# NavCom_Board_3.net
KiCad netlist of a schematic drawn in EAGLE
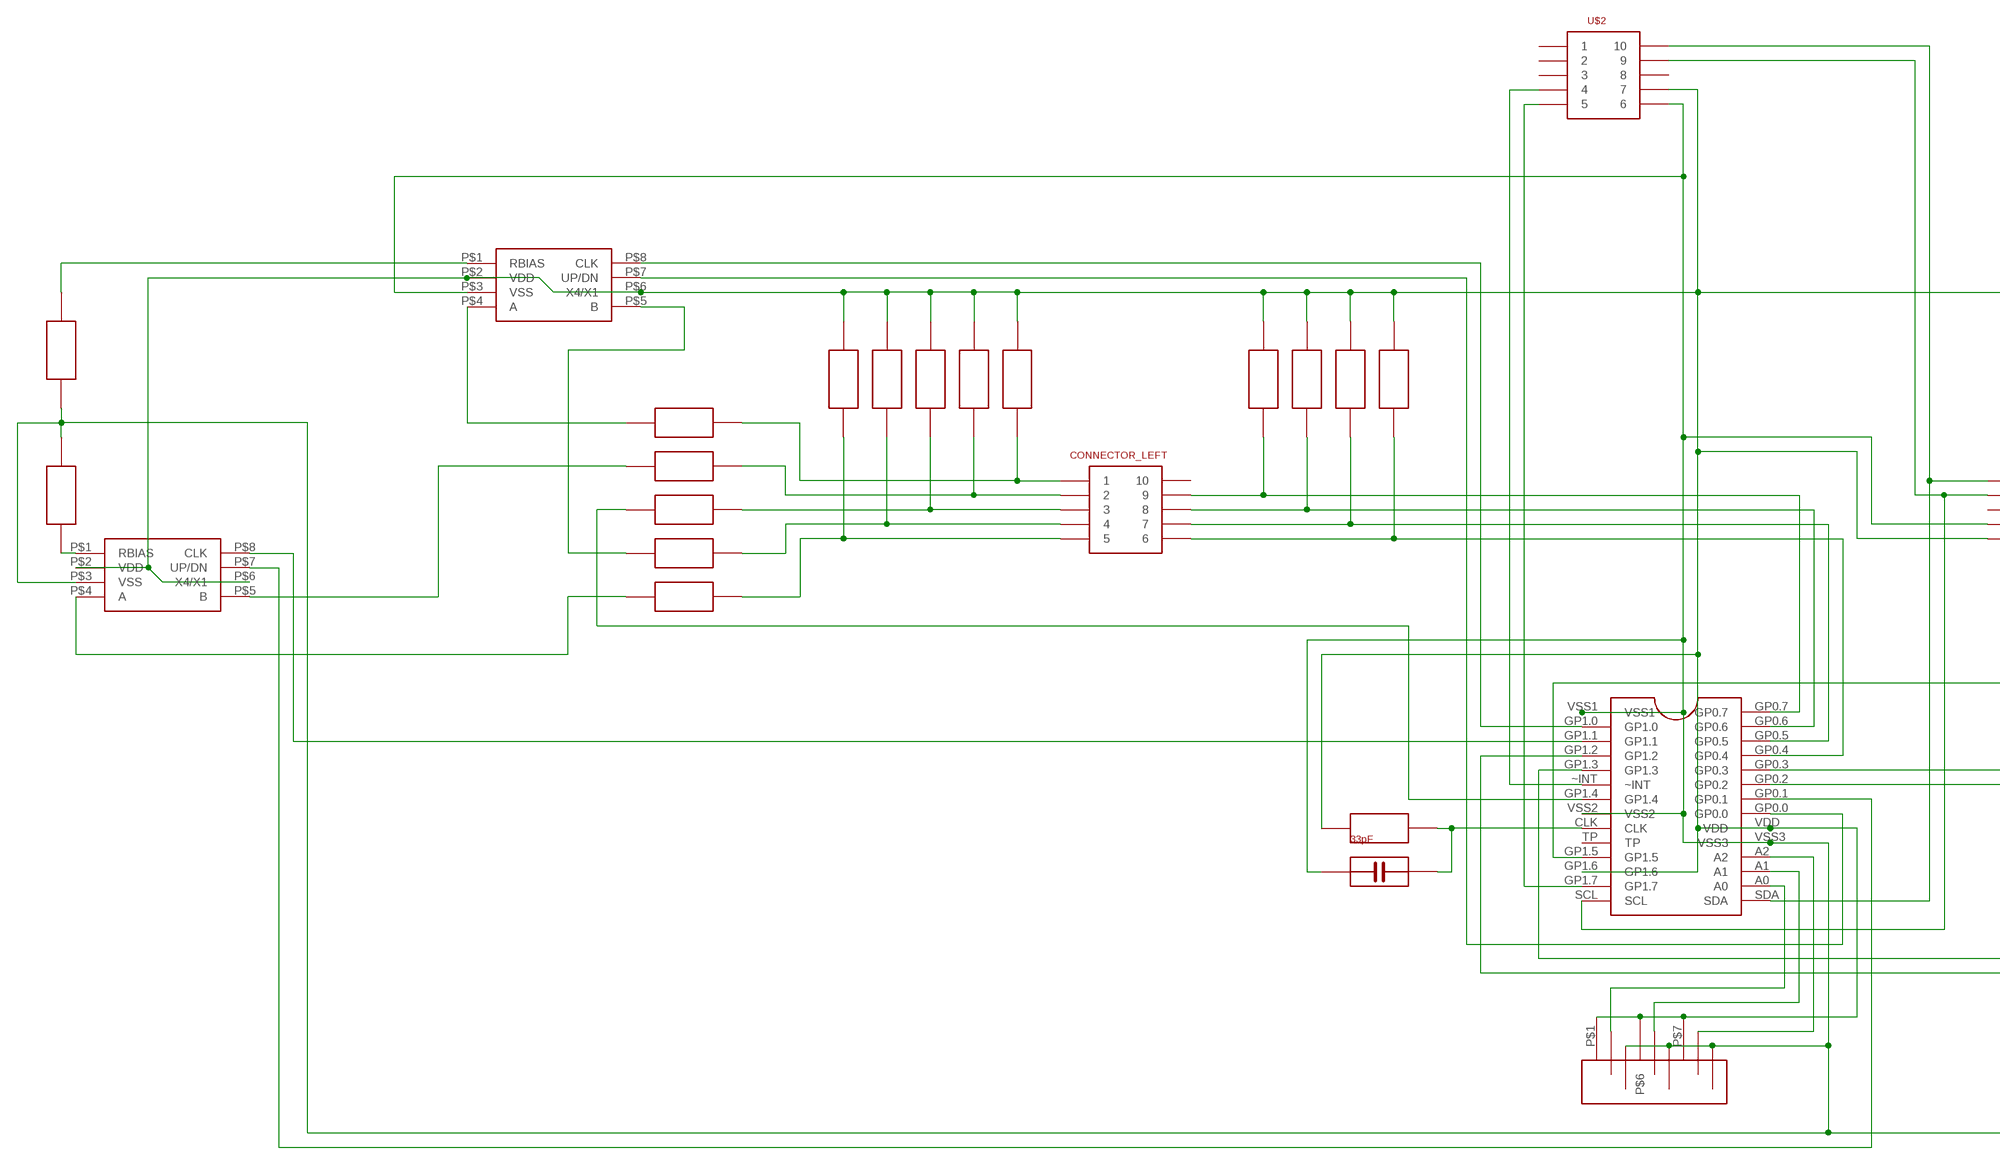
[diagram p0: schematic, sheet 1, part 1 of 2]
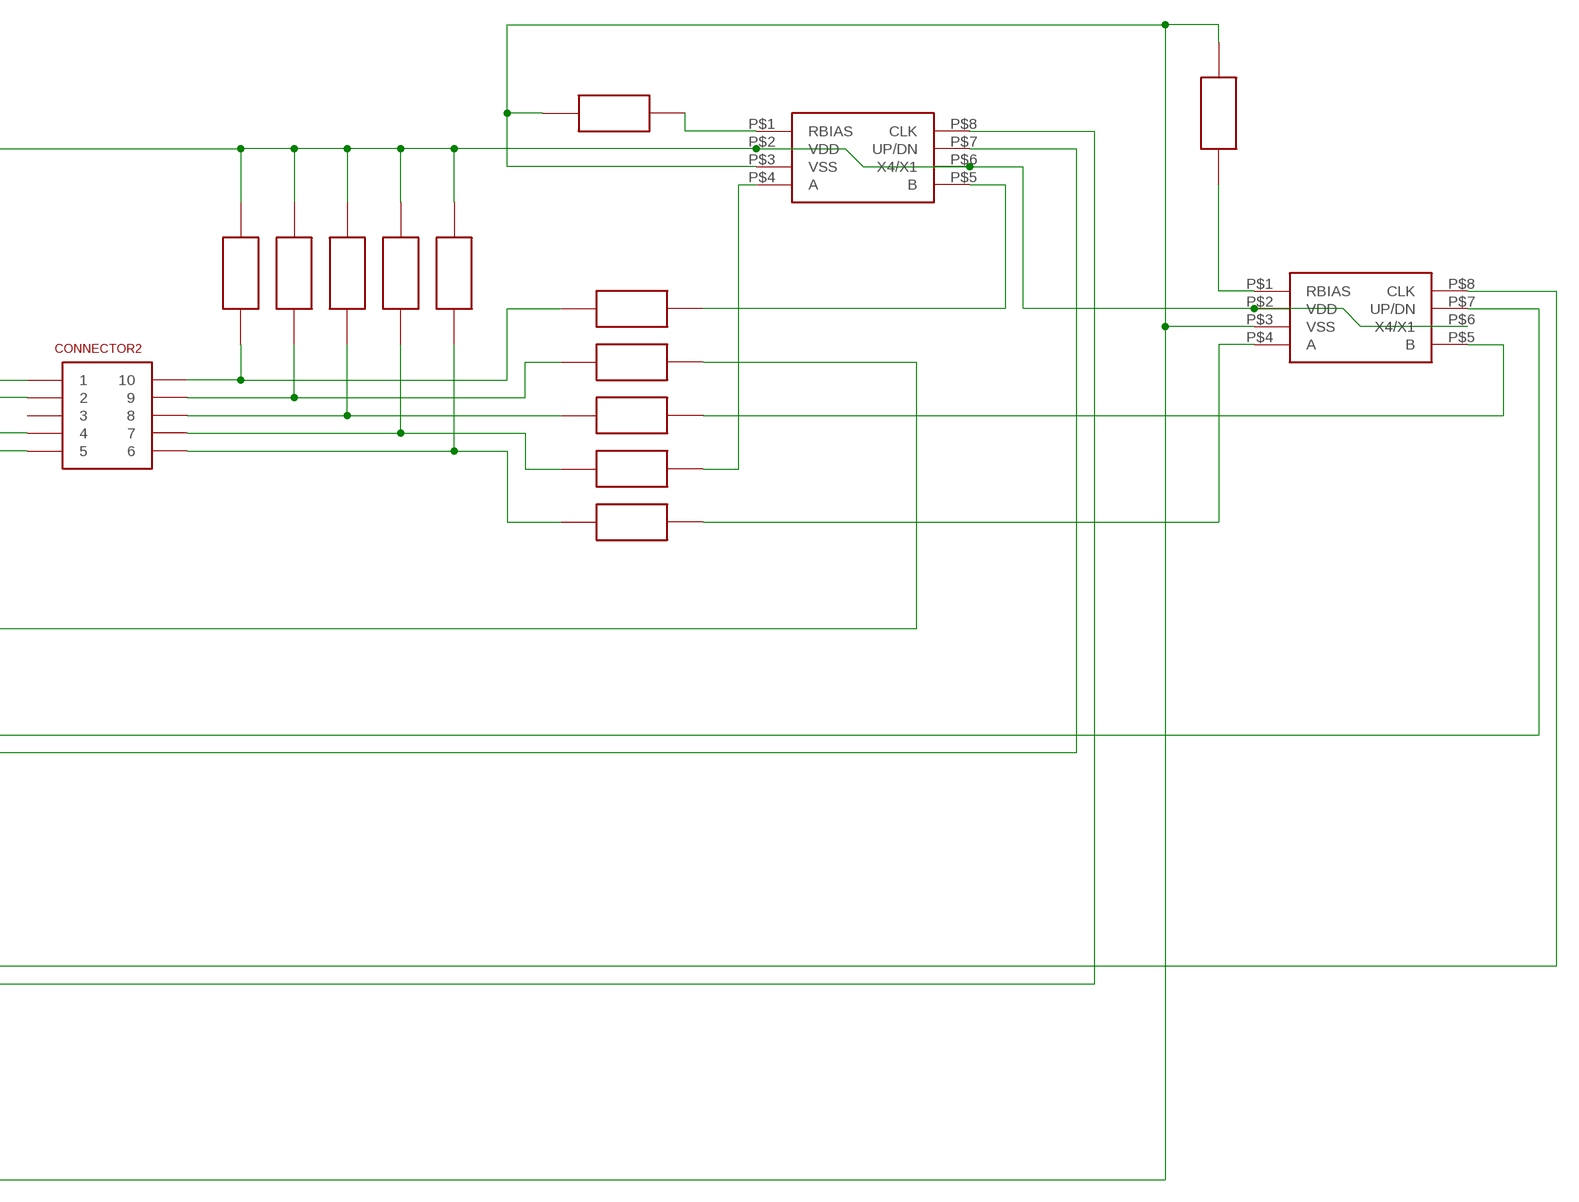
[diagram p1: schematic, sheet 1, part 2 of 2]

(export (version "E")
  (design (tool "Eeschema 10.0.6"))
  (components
    (comp (ref "33PF")
      (value "33pF")
      (footprint "eagle-import:KONDENZATOR")
      (libsource (lib "eagle-import") (part "KONDENZATOR"))
    )
    (comp (ref "CONNECTOR2")
      (value "LISTA_2X5")
      (footprint "eagle-import:LISTA_2X5")
      (libsource (lib "eagle-import") (part "LISTA_2X5"))
    )
    (comp (ref "CONNECTOR_LEFT")
      (value "LISTA_2X5")
      (footprint "eagle-import:LISTA_2X5")
      (libsource (lib "eagle-import") (part "LISTA_2X5"))
    )
    (comp (ref "U$1")
      (value "MCP23016")
      (footprint "eagle-import:MCP23016")
      (libsource (lib "eagle-import") (part "MCP23016"))
    )
    (comp (ref "U$2")
      (value "LISTA_2X5")
      (footprint "eagle-import:LISTA_2X5")
      (libsource (lib "eagle-import") (part "LISTA_2X5"))
    )
    (comp (ref "U$3")
      (value "LS7084")
      (footprint "eagle-import:LS7084")
      (libsource (lib "eagle-import") (part "LS7084"))
    )
    (comp (ref "U$4")
      (value "LS7084")
      (footprint "eagle-import:LS7084")
      (libsource (lib "eagle-import") (part "LS7084"))
    )
    (comp (ref "U$5")
      (value "LS7084")
      (footprint "eagle-import:LS7084")
      (libsource (lib "eagle-import") (part "LS7084"))
    )
    (comp (ref "U$6")
      (value "LS7084")
      (footprint "eagle-import:LS7084")
      (libsource (lib "eagle-import") (part "LS7084"))
    )
    (comp (ref "U$7")
      (value "REZISTOR")
      (footprint "eagle-import:REZISTOR")
      (libsource (lib "eagle-import") (part "REZISTOR"))
    )
    (comp (ref "U$8")
      (value "REZISTOR")
      (footprint "eagle-import:REZISTOR")
      (libsource (lib "eagle-import") (part "REZISTOR"))
    )
    (comp (ref "U$9")
      (value "REZISTOR")
      (footprint "eagle-import:REZISTOR")
      (libsource (lib "eagle-import") (part "REZISTOR"))
    )
    (comp (ref "U$10")
      (value "REZISTOR")
      (footprint "eagle-import:REZISTOR")
      (libsource (lib "eagle-import") (part "REZISTOR"))
    )
    (comp (ref "U$11")
      (value "ADRESA_0..2")
      (footprint "eagle-import:ADRESA_0..2")
      (libsource (lib "eagle-import") (part "ADRESA_0..2"))
    )
    (comp (ref "U$12")
      (value "REZISTOR")
      (footprint "eagle-import:REZISTOR")
      (libsource (lib "eagle-import") (part "REZISTOR"))
    )
    (comp (ref "U$13")
      (value "REZISTOR")
      (footprint "eagle-import:REZISTOR")
      (libsource (lib "eagle-import") (part "REZISTOR"))
    )
    (comp (ref "U$14")
      (value "REZISTOR")
      (footprint "eagle-import:REZISTOR")
      (libsource (lib "eagle-import") (part "REZISTOR"))
    )
    (comp (ref "U$15")
      (value "REZISTOR")
      (footprint "eagle-import:REZISTOR")
      (libsource (lib "eagle-import") (part "REZISTOR"))
    )
    (comp (ref "U$16")
      (value "REZISTOR")
      (footprint "eagle-import:REZISTOR")
      (libsource (lib "eagle-import") (part "REZISTOR"))
    )
    (comp (ref "U$17")
      (value "REZISTOR")
      (footprint "eagle-import:REZISTOR")
      (libsource (lib "eagle-import") (part "REZISTOR"))
    )
    (comp (ref "U$18")
      (value "REZISTOR")
      (footprint "eagle-import:REZISTOR")
      (libsource (lib "eagle-import") (part "REZISTOR"))
    )
    (comp (ref "U$19")
      (value "REZISTOR")
      (footprint "eagle-import:REZISTOR")
      (libsource (lib "eagle-import") (part "REZISTOR"))
    )
    (comp (ref "U$20")
      (value "REZISTOR")
      (footprint "eagle-import:REZISTOR")
      (libsource (lib "eagle-import") (part "REZISTOR"))
    )
    (comp (ref "U$21")
      (value "REZISTOR")
      (footprint "eagle-import:REZISTOR")
      (libsource (lib "eagle-import") (part "REZISTOR"))
    )
    (comp (ref "U$22")
      (value "REZISTOR")
      (footprint "eagle-import:REZISTOR")
      (libsource (lib "eagle-import") (part "REZISTOR"))
    )
    (comp (ref "U$23")
      (value "3.9k")
      (footprint "eagle-import:REZISTOR")
      (libsource (lib "eagle-import") (part "REZISTOR"))
    )
    (comp (ref "U$27")
      (value "470M")
      (footprint "eagle-import:REZISTOR")
      (libsource (lib "eagle-import") (part "REZISTOR"))
    )
    (comp (ref "U$29")
      (value "REZISTOR")
      (footprint "eagle-import:REZISTOR")
      (libsource (lib "eagle-import") (part "REZISTOR"))
    )
    (comp (ref "U$30")
      (value "REZISTOR")
      (footprint "eagle-import:REZISTOR")
      (libsource (lib "eagle-import") (part "REZISTOR"))
    )
    (comp (ref "U$31")
      (value "REZISTOR")
      (footprint "eagle-import:REZISTOR")
      (libsource (lib "eagle-import") (part "REZISTOR"))
    )
    (comp (ref "U$32")
      (value "REZISTOR")
      (footprint "eagle-import:REZISTOR")
      (libsource (lib "eagle-import") (part "REZISTOR"))
    )
    (comp (ref "U$33")
      (value "REZISTOR")
      (footprint "eagle-import:REZISTOR")
      (libsource (lib "eagle-import") (part "REZISTOR"))
    )
    (comp (ref "U$34")
      (value "470M")
      (footprint "eagle-import:REZISTOR")
      (libsource (lib "eagle-import") (part "REZISTOR"))
    )
    (comp (ref "U$35")
      (value "REZISTOR")
      (footprint "eagle-import:REZISTOR")
      (libsource (lib "eagle-import") (part "REZISTOR"))
    )
    (comp (ref "U$36")
      (value "REZISTOR")
      (footprint "eagle-import:REZISTOR")
      (libsource (lib "eagle-import") (part "REZISTOR"))
    )
    (comp (ref "U$38")
      (value "REZISTOR")
      (footprint "eagle-import:REZISTOR")
      (libsource (lib "eagle-import") (part "REZISTOR"))
    )
    (comp (ref "U$39")
      (value "REZISTOR")
      (footprint "eagle-import:REZISTOR")
      (libsource (lib "eagle-import") (part "REZISTOR"))
    )
    (comp (ref "U$40")
      (value "470M")
      (footprint "eagle-import:REZISTOR")
      (libsource (lib "eagle-import") (part "REZISTOR"))
    )
    (comp (ref "U$41")
      (value "470M")
      (footprint "eagle-import:REZISTOR")
      (libsource (lib "eagle-import") (part "REZISTOR"))
    )
  )
  (nets
    (net (code "1") (name "Net-(33PF-PadP$2)") (class "Default")
      (node (ref "33PF") (pin "P$2") (pinfunction "P$2_P$2") (pintype "bidirectional"))
      (node (ref "U$1") (pin "CLK") (pinfunction "CLK_CLK") (pintype "bidirectional"))
      (node (ref "U$23") (pin "P$2") (pinfunction "P$2_P$2") (pintype "bidirectional"))
    )
    (net (code "2") (name "Net-(CONNECTOR2-Pad1)") (class "Default")
      (node (ref "CONNECTOR2") (pin "1") (pinfunction "1_1") (pintype "bidirectional"))
      (node (ref "U$1") (pin "SDA") (pinfunction "SDA_SDA") (pintype "bidirectional"))
      (node (ref "U$2") (pin "10") (pinfunction "10_10") (pintype "bidirectional"))
    )
    (net (code "3") (name "Net-(CONNECTOR2-Pad2)") (class "Default")
      (node (ref "CONNECTOR2") (pin "2") (pinfunction "2_2") (pintype "bidirectional"))
      (node (ref "U$1") (pin "SCL") (pinfunction "SCL_SCL") (pintype "bidirectional"))
      (node (ref "U$2") (pin "9") (pinfunction "9_9") (pintype "bidirectional"))
    )
    (net (code "4") (name "Net-(CONNECTOR2-Pad6)") (class "Default")
      (node (ref "CONNECTOR2") (pin "6") (pinfunction "6_6") (pintype "bidirectional"))
      (node (ref "U$12") (pin "P$1") (pinfunction "P$1_P$1") (pintype "bidirectional"))
      (node (ref "U$33") (pin "P$2") (pinfunction "P$2_P$2") (pintype "bidirectional"))
    )
    (net (code "5") (name "Net-(CONNECTOR2-Pad7)") (class "Default")
      (node (ref "CONNECTOR2") (pin "7") (pinfunction "7_7") (pintype "bidirectional"))
      (node (ref "U$17") (pin "P$1") (pinfunction "P$1_P$1") (pintype "bidirectional"))
      (node (ref "U$32") (pin "P$2") (pinfunction "P$2_P$2") (pintype "bidirectional"))
    )
    (net (code "6") (name "Net-(CONNECTOR2-Pad8)") (class "Default")
      (node (ref "CONNECTOR2") (pin "8") (pinfunction "8_8") (pintype "bidirectional"))
      (node (ref "U$10") (pin "P$1") (pinfunction "P$1_P$1") (pintype "bidirectional"))
      (node (ref "U$31") (pin "P$2") (pinfunction "P$2_P$2") (pintype "bidirectional"))
    )
    (net (code "7") (name "Net-(CONNECTOR2-Pad9)") (class "Default")
      (node (ref "CONNECTOR2") (pin "9") (pinfunction "9_9") (pintype "bidirectional"))
      (node (ref "U$30") (pin "P$2") (pinfunction "P$2_P$2") (pintype "bidirectional"))
      (node (ref "U$9") (pin "P$1") (pinfunction "P$1_P$1") (pintype "bidirectional"))
    )
    (net (code "8") (name "Net-(CONNECTOR2-Pad10)") (class "Default")
      (node (ref "CONNECTOR2") (pin "10") (pinfunction "10_10") (pintype "bidirectional"))
      (node (ref "U$29") (pin "P$2") (pinfunction "P$2_P$2") (pintype "bidirectional"))
      (node (ref "U$7") (pin "P$1") (pinfunction "P$1_P$1") (pintype "bidirectional"))
    )
    (net (code "9") (name "Net-(CONNECTOR_LEFT-Pad1)") (class "Default")
      (node (ref "CONNECTOR_LEFT") (pin "1") (pinfunction "1_1") (pintype "bidirectional"))
      (node (ref "U$16") (pin "P$2") (pinfunction "P$2_P$2") (pintype "bidirectional"))
      (node (ref "U$35") (pin "P$2") (pinfunction "P$2_P$2") (pintype "bidirectional"))
    )
    (net (code "10") (name "Net-(CONNECTOR_LEFT-Pad2)") (class "Default")
      (node (ref "CONNECTOR_LEFT") (pin "2") (pinfunction "2_2") (pintype "bidirectional"))
      (node (ref "U$13") (pin "P$2") (pinfunction "P$2_P$2") (pintype "bidirectional"))
      (node (ref "U$36") (pin "P$2") (pinfunction "P$2_P$2") (pintype "bidirectional"))
    )
    (net (code "11") (name "Net-(CONNECTOR_LEFT-Pad3)") (class "Default")
      (node (ref "CONNECTOR_LEFT") (pin "3") (pinfunction "3_3") (pintype "bidirectional"))
      (node (ref "U$14") (pin "P$2") (pinfunction "P$2_P$2") (pintype "bidirectional"))
      (node (ref "U$22") (pin "P$2") (pinfunction "P$2_P$2") (pintype "bidirectional"))
    )
    (net (code "12") (name "Net-(CONNECTOR_LEFT-Pad4)") (class "Default")
      (node (ref "CONNECTOR_LEFT") (pin "4") (pinfunction "4_4") (pintype "bidirectional"))
      (node (ref "U$15") (pin "P$2") (pinfunction "P$2_P$2") (pintype "bidirectional"))
      (node (ref "U$38") (pin "P$2") (pinfunction "P$2_P$2") (pintype "bidirectional"))
    )
    (net (code "13") (name "Net-(CONNECTOR_LEFT-Pad5)") (class "Default")
      (node (ref "CONNECTOR_LEFT") (pin "5") (pinfunction "5_5") (pintype "bidirectional"))
      (node (ref "U$18") (pin "P$2") (pinfunction "P$2_P$2") (pintype "bidirectional"))
      (node (ref "U$39") (pin "P$2") (pinfunction "P$2_P$2") (pintype "bidirectional"))
    )
    (net (code "14") (name "Net-(CONNECTOR_LEFT-Pad6)") (class "Default")
      (node (ref "CONNECTOR_LEFT") (pin "6") (pinfunction "6_6") (pintype "bidirectional"))
      (node (ref "U$1") (pin "GP0.4") (pinfunction "GP0.4_GP0.4") (pintype "bidirectional"))
      (node (ref "U$21") (pin "P$2") (pinfunction "P$2_P$2") (pintype "bidirectional"))
    )
    (net (code "15") (name "Net-(CONNECTOR_LEFT-Pad7)") (class "Default")
      (node (ref "CONNECTOR_LEFT") (pin "7") (pinfunction "7_7") (pintype "bidirectional"))
      (node (ref "U$1") (pin "GP0.5") (pinfunction "GP0.5_GP0.5") (pintype "bidirectional"))
      (node (ref "U$20") (pin "P$2") (pinfunction "P$2_P$2") (pintype "bidirectional"))
    )
    (net (code "16") (name "Net-(CONNECTOR_LEFT-Pad8)") (class "Default")
      (node (ref "CONNECTOR_LEFT") (pin "8") (pinfunction "8_8") (pintype "bidirectional"))
      (node (ref "U$1") (pin "GP0.6") (pinfunction "GP0.6_GP0.6") (pintype "bidirectional"))
      (node (ref "U$19") (pin "P$2") (pinfunction "P$2_P$2") (pintype "bidirectional"))
    )
    (net (code "17") (name "Net-(CONNECTOR_LEFT-Pad9)") (class "Default")
      (node (ref "CONNECTOR_LEFT") (pin "9") (pinfunction "9_9") (pintype "bidirectional"))
      (node (ref "U$1") (pin "GP0.7") (pinfunction "GP0.7_GP0.7") (pintype "bidirectional"))
      (node (ref "U$8") (pin "P$2") (pinfunction "P$2_P$2") (pintype "bidirectional"))
    )
    (net (code "18") (name "Net-(U$1-PadA0)") (class "Default")
      (node (ref "U$1") (pin "A0") (pinfunction "A0_A0") (pintype "bidirectional"))
      (node (ref "U$11") (pin "P$2") (pinfunction "P$2_P$2") (pintype "bidirectional"))
    )
    (net (code "19") (name "Net-(U$1-PadA1)") (class "Default")
      (node (ref "U$1") (pin "A1") (pinfunction "A1_A1") (pintype "bidirectional"))
      (node (ref "U$11") (pin "P$5") (pinfunction "P$5_P$5") (pintype "bidirectional"))
    )
    (net (code "20") (name "Net-(U$1-PadA2)") (class "Default")
      (node (ref "U$1") (pin "A2") (pinfunction "A2_A2") (pintype "bidirectional"))
      (node (ref "U$11") (pin "P$8") (pinfunction "P$8_P$8") (pintype "bidirectional"))
    )
    (net (code "21") (name "Net-(U$1-PadGP1.4)") (class "Default")
      (node (ref "U$1") (pin "GP1.4") (pinfunction "GP1.4_GP1.4") (pintype "bidirectional"))
      (node (ref "U$22") (pin "P$1") (pinfunction "P$1_P$1") (pintype "bidirectional"))
    )
    (net (code "22") (name "Net-(U$1-PadGP1.5)") (class "Default")
      (node (ref "U$1") (pin "GP1.5") (pinfunction "GP1.5_GP1.5") (pintype "bidirectional"))
      (node (ref "U$30") (pin "P$1") (pinfunction "P$1_P$1") (pintype "bidirectional"))
    )
    (net (code "23") (name "Net-(U$1-PadGP1.7)") (class "Default")
      (node (ref "U$1") (pin "GP1.7") (pinfunction "GP1.7_GP1.7") (pintype "bidirectional"))
      (node (ref "U$2") (pin "5") (pinfunction "5_5") (pintype "bidirectional"))
    )
    (net (code "24") (name "Net-(U$1-~{INT})") (class "Default")
      (node (ref "U$1") (pin "~INT") (pinfunction "~{INT}_~INT") (pintype "bidirectional"))
      (node (ref "U$2") (pin "4") (pinfunction "4_4") (pintype "bidirectional"))
    )
    (net (code "25") (name "Net-(U$3-A)") (class "Default")
      (node (ref "U$3") (pin "P$4") (pinfunction "A_P$4") (pintype "bidirectional"))
      (node (ref "U$35") (pin "P$1") (pinfunction "P$1_P$1") (pintype "bidirectional"))
    )
    (net (code "26") (name "Net-(U$3-B)") (class "Default")
      (node (ref "U$3") (pin "P$5") (pinfunction "B_P$5") (pintype "bidirectional"))
      (node (ref "U$38") (pin "P$1") (pinfunction "P$1_P$1") (pintype "bidirectional"))
    )
    (net (code "27") (name "Net-(U$3-CLK)") (class "Default")
      (node (ref "U$1") (pin "GP1.0") (pinfunction "GP1.0_GP1.0") (pintype "bidirectional"))
      (node (ref "U$3") (pin "P$8") (pinfunction "CLK_P$8") (pintype "bidirectional"))
    )
    (net (code "28") (name "Net-(U$3-RBIAS)") (class "Default")
      (node (ref "U$3") (pin "P$1") (pinfunction "RBIAS_P$1") (pintype "bidirectional"))
      (node (ref "U$40") (pin "P$2") (pinfunction "P$2_P$2") (pintype "bidirectional"))
    )
    (net (code "29") (name "Net-(U$3-UP{slash}DN)") (class "Default")
      (node (ref "U$1") (pin "GP0.0") (pinfunction "GP0.0_GP0.0") (pintype "bidirectional"))
      (node (ref "U$3") (pin "P$7") (pinfunction "UP/DN_P$7") (pintype "bidirectional"))
    )
    (net (code "30") (name "Net-(U$3-VDD)") (class "Default")
      (node (ref "CONNECTOR2") (pin "5") (pinfunction "5_5") (pintype "bidirectional"))
      (node (ref "U$1") (pin "GP1.6") (pinfunction "GP1.6_GP1.6") (pintype "bidirectional"))
      (node (ref "U$1") (pin "VDD") (pinfunction "VDD_VDD") (pintype "bidirectional"))
      (node (ref "U$10") (pin "P$2") (pinfunction "P$2_P$2") (pintype "bidirectional"))
      (node (ref "U$11") (pin "P$1") (pinfunction "P$1_P$1") (pintype "bidirectional"))
      (node (ref "U$11") (pin "P$6") (pinfunction "P$6_P$6") (pintype "bidirectional"))
      (node (ref "U$11") (pin "P$7") (pinfunction "P$7_P$7") (pintype "bidirectional"))
      (node (ref "U$12") (pin "P$2") (pinfunction "P$2_P$2") (pintype "bidirectional"))
      (node (ref "U$13") (pin "P$1") (pinfunction "P$1_P$1") (pintype "bidirectional"))
      (node (ref "U$14") (pin "P$1") (pinfunction "P$1_P$1") (pintype "bidirectional"))
      (node (ref "U$15") (pin "P$1") (pinfunction "P$1_P$1") (pintype "bidirectional"))
      (node (ref "U$16") (pin "P$1") (pinfunction "P$1_P$1") (pintype "bidirectional"))
      (node (ref "U$17") (pin "P$2") (pinfunction "P$2_P$2") (pintype "bidirectional"))
      (node (ref "U$18") (pin "P$1") (pinfunction "P$1_P$1") (pintype "bidirectional"))
      (node (ref "U$19") (pin "P$1") (pinfunction "P$1_P$1") (pintype "bidirectional"))
      (node (ref "U$2") (pin "7") (pinfunction "7_7") (pintype "bidirectional"))
      (node (ref "U$20") (pin "P$1") (pinfunction "P$1_P$1") (pintype "bidirectional"))
      (node (ref "U$21") (pin "P$1") (pinfunction "P$1_P$1") (pintype "bidirectional"))
      (node (ref "U$23") (pin "P$1") (pinfunction "P$1_P$1") (pintype "bidirectional"))
      (node (ref "U$3") (pin "P$2") (pinfunction "VDD_P$2") (pintype "bidirectional"))
      (node (ref "U$3") (pin "P$6") (pinfunction "X4/X1_P$6") (pintype "bidirectional"))
      (node (ref "U$4") (pin "P$2") (pinfunction "VDD_P$2") (pintype "bidirectional"))
      (node (ref "U$4") (pin "P$6") (pinfunction "X4/X1_P$6") (pintype "bidirectional"))
      (node (ref "U$5") (pin "P$2") (pinfunction "VDD_P$2") (pintype "bidirectional"))
      (node (ref "U$5") (pin "P$6") (pinfunction "X4/X1_P$6") (pintype "bidirectional"))
      (node (ref "U$6") (pin "P$2") (pinfunction "VDD_P$2") (pintype "bidirectional"))
      (node (ref "U$6") (pin "P$6") (pinfunction "X4/X1_P$6") (pintype "bidirectional"))
      (node (ref "U$7") (pin "P$2") (pinfunction "P$2_P$2") (pintype "bidirectional"))
      (node (ref "U$8") (pin "P$1") (pinfunction "P$1_P$1") (pintype "bidirectional"))
      (node (ref "U$9") (pin "P$2") (pinfunction "P$2_P$2") (pintype "bidirectional"))
    )
    (net (code "31") (name "Net-(U$3-VSS)") (class "Default")
      (node (ref "33PF") (pin "P$1") (pinfunction "P$1_P$1") (pintype "bidirectional"))
      (node (ref "CONNECTOR2") (pin "4") (pinfunction "4_4") (pintype "bidirectional"))
      (node (ref "U$1") (pin "VSS1") (pinfunction "VSS1_VSS1") (pintype "bidirectional"))
      (node (ref "U$1") (pin "VSS2") (pinfunction "VSS2_VSS2") (pintype "bidirectional"))
      (node (ref "U$1") (pin "VSS3") (pinfunction "VSS3_VSS3") (pintype "bidirectional"))
      (node (ref "U$11") (pin "P$3") (pinfunction "P$3_P$3") (pintype "bidirectional"))
      (node (ref "U$11") (pin "P$4") (pinfunction "P$4_P$4") (pintype "bidirectional"))
      (node (ref "U$11") (pin "P$9") (pinfunction "P$9_P$9") (pintype "bidirectional"))
      (node (ref "U$2") (pin "6") (pinfunction "6_6") (pintype "bidirectional"))
      (node (ref "U$27") (pin "P$2") (pinfunction "P$2_P$2") (pintype "bidirectional"))
      (node (ref "U$3") (pin "P$3") (pinfunction "VSS_P$3") (pintype "bidirectional"))
      (node (ref "U$34") (pin "P$1") (pinfunction "P$1_P$1") (pintype "bidirectional"))
      (node (ref "U$4") (pin "P$3") (pinfunction "VSS_P$3") (pintype "bidirectional"))
      (node (ref "U$40") (pin "P$1") (pinfunction "P$1_P$1") (pintype "bidirectional"))
      (node (ref "U$41") (pin "P$1") (pinfunction "P$1_P$1") (pintype "bidirectional"))
      (node (ref "U$5") (pin "P$3") (pinfunction "VSS_P$3") (pintype "bidirectional"))
      (node (ref "U$6") (pin "P$3") (pinfunction "VSS_P$3") (pintype "bidirectional"))
    )
    (net (code "32") (name "Net-(U$4-A)") (class "Default")
      (node (ref "U$32") (pin "P$1") (pinfunction "P$1_P$1") (pintype "bidirectional"))
      (node (ref "U$4") (pin "P$4") (pinfunction "A_P$4") (pintype "bidirectional"))
    )
    (net (code "33") (name "Net-(U$4-B)") (class "Default")
      (node (ref "U$29") (pin "P$1") (pinfunction "P$1_P$1") (pintype "bidirectional"))
      (node (ref "U$4") (pin "P$5") (pinfunction "B_P$5") (pintype "bidirectional"))
    )
    (net (code "34") (name "Net-(U$4-CLK)") (class "Default")
      (node (ref "U$1") (pin "GP1.2") (pinfunction "GP1.2_GP1.2") (pintype "bidirectional"))
      (node (ref "U$4") (pin "P$8") (pinfunction "CLK_P$8") (pintype "bidirectional"))
    )
    (net (code "35") (name "Net-(U$4-RBIAS)") (class "Default")
      (node (ref "U$27") (pin "P$1") (pinfunction "P$1_P$1") (pintype "bidirectional"))
      (node (ref "U$4") (pin "P$1") (pinfunction "RBIAS_P$1") (pintype "bidirectional"))
    )
    (net (code "36") (name "Net-(U$4-UP{slash}DN)") (class "Default")
      (node (ref "U$1") (pin "GP0.2") (pinfunction "GP0.2_GP0.2") (pintype "bidirectional"))
      (node (ref "U$4") (pin "P$7") (pinfunction "UP/DN_P$7") (pintype "bidirectional"))
    )
    (net (code "37") (name "Net-(U$5-A)") (class "Default")
      (node (ref "U$33") (pin "P$1") (pinfunction "P$1_P$1") (pintype "bidirectional"))
      (node (ref "U$5") (pin "P$4") (pinfunction "A_P$4") (pintype "bidirectional"))
    )
    (net (code "38") (name "Net-(U$5-B)") (class "Default")
      (node (ref "U$31") (pin "P$1") (pinfunction "P$1_P$1") (pintype "bidirectional"))
      (node (ref "U$5") (pin "P$5") (pinfunction "B_P$5") (pintype "bidirectional"))
    )
    (net (code "39") (name "Net-(U$5-CLK)") (class "Default")
      (node (ref "U$1") (pin "GP1.3") (pinfunction "GP1.3_GP1.3") (pintype "bidirectional"))
      (node (ref "U$5") (pin "P$8") (pinfunction "CLK_P$8") (pintype "bidirectional"))
    )
    (net (code "40") (name "Net-(U$5-RBIAS)") (class "Default")
      (node (ref "U$34") (pin "P$2") (pinfunction "P$2_P$2") (pintype "bidirectional"))
      (node (ref "U$5") (pin "P$1") (pinfunction "RBIAS_P$1") (pintype "bidirectional"))
    )
    (net (code "41") (name "Net-(U$5-UP{slash}DN)") (class "Default")
      (node (ref "U$1") (pin "GP0.3") (pinfunction "GP0.3_GP0.3") (pintype "bidirectional"))
      (node (ref "U$5") (pin "P$7") (pinfunction "UP/DN_P$7") (pintype "bidirectional"))
    )
    (net (code "42") (name "Net-(U$6-A)") (class "Default")
      (node (ref "U$39") (pin "P$1") (pinfunction "P$1_P$1") (pintype "bidirectional"))
      (node (ref "U$6") (pin "P$4") (pinfunction "A_P$4") (pintype "bidirectional"))
    )
    (net (code "43") (name "Net-(U$6-B)") (class "Default")
      (node (ref "U$36") (pin "P$1") (pinfunction "P$1_P$1") (pintype "bidirectional"))
      (node (ref "U$6") (pin "P$5") (pinfunction "B_P$5") (pintype "bidirectional"))
    )
    (net (code "44") (name "Net-(U$6-CLK)") (class "Default")
      (node (ref "U$1") (pin "GP1.1") (pinfunction "GP1.1_GP1.1") (pintype "bidirectional"))
      (node (ref "U$6") (pin "P$8") (pinfunction "CLK_P$8") (pintype "bidirectional"))
    )
    (net (code "45") (name "Net-(U$6-RBIAS)") (class "Default")
      (node (ref "U$41") (pin "P$2") (pinfunction "P$2_P$2") (pintype "bidirectional"))
      (node (ref "U$6") (pin "P$1") (pinfunction "RBIAS_P$1") (pintype "bidirectional"))
    )
    (net (code "46") (name "Net-(U$6-UP{slash}DN)") (class "Default")
      (node (ref "U$1") (pin "GP0.1") (pinfunction "GP0.1_GP0.1") (pintype "bidirectional"))
      (node (ref "U$6") (pin "P$7") (pinfunction "UP/DN_P$7") (pintype "bidirectional"))
    )
    (net (code "47") (name "unconnected-(CONNECTOR2-Pad3)") (class "Default")
      (node (ref "CONNECTOR2") (pin "3") (pinfunction "3_3") (pintype "bidirectional"))
    )
    (net (code "48") (name "unconnected-(CONNECTOR_LEFT-Pad10)") (class "Default")
      (node (ref "CONNECTOR_LEFT") (pin "10") (pinfunction "10_10") (pintype "bidirectional"))
    )
    (net (code "49") (name "unconnected-(U$1-PadTP)") (class "Default")
      (node (ref "U$1") (pin "TP") (pinfunction "TP_TP") (pintype "bidirectional"))
    )
    (net (code "50") (name "unconnected-(U$2-Pad1)") (class "Default")
      (node (ref "U$2") (pin "1") (pinfunction "1_1") (pintype "bidirectional"))
    )
    (net (code "51") (name "unconnected-(U$2-Pad2)") (class "Default")
      (node (ref "U$2") (pin "2") (pinfunction "2_2") (pintype "bidirectional"))
    )
    (net (code "52") (name "unconnected-(U$2-Pad3)") (class "Default")
      (node (ref "U$2") (pin "3") (pinfunction "3_3") (pintype "bidirectional"))
    )
    (net (code "53") (name "unconnected-(U$2-Pad8)") (class "Default")
      (node (ref "U$2") (pin "8") (pinfunction "8_8") (pintype "bidirectional"))
    )
  )
)
